# led_fading_circuit.net
KiCad netlist of a schematic drawn in EAGLE
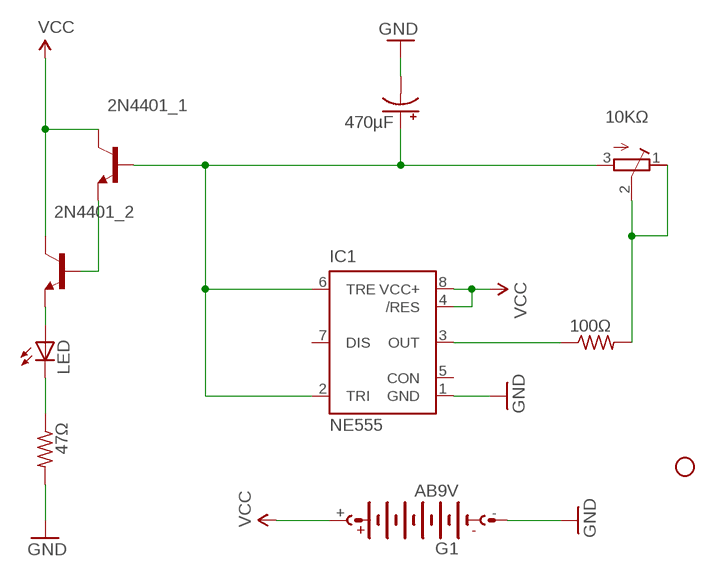
[diagram p0: schematic, sheet 1]

(export (version "E")
  (design (tool "Eeschema 10.0.6"))
  (components
    (comp (ref "2N4401_1")
      (value "-NPN-TO92-EBC")
      (footprint "eagle-import:TO92-EBC")
      (libsource (lib "eagle-import") (part "-NPN-TO92-EBC"))
    )
    (comp (ref "2N4401_2")
      (value "-NPN-TO92-EBC")
      (footprint "eagle-import:TO92-EBC")
      (libsource (lib "eagle-import") (part "-NPN-TO92-EBC"))
    )
    (comp (ref "10KΩ")
      (value "R-TRIMMT93XA")
      (footprint "eagle-import:RTRIMT93XA")
      (libsource (lib "eagle-import") (part "R-TRIMMT93XA"))
    )
    (comp (ref "47Ω")
      (value "R-US_0204/7")
      (footprint "eagle-import:0204_7")
      (libsource (lib "eagle-import") (part "R-US_0204/7"))
    )
    (comp (ref "100Ω")
      (value "R-US_0207/10")
      (footprint "eagle-import:0207_10")
      (libsource (lib "eagle-import") (part "R-US_0207/10"))
    )
    (comp (ref "470µF")
      (value "CPOL-USE2.5-6")
      (footprint "eagle-import:E2,5-6")
      (libsource (lib "eagle-import") (part "CPOL-USE2.5-6"))
    )
    (comp (ref "G1")
      (value "AB9V")
      (footprint "eagle-import:AB9V")
      (libsource (lib "eagle-import") (part "AB9V"))
    )
    (comp (ref "IC1")
      (value "NE555")
      (footprint "eagle-import:DIL-08")
      (fields (field (name "MF") "Arrow Electronics") (field (name "MPN") "NE555N"))
      (libsource (lib "eagle-import") (part "NE555"))
    )
    (comp (ref "LED")
      (value "LED5MM")
      (footprint "eagle-import:LED5MM")
      (libsource (lib "eagle-import") (part "LED5MM"))
    )
    (comp (ref "STANDOFF1")
      (value "STAND-OFF")
      (footprint "eagle-import:STAND-OFF")
      (libsource (lib "eagle-import") (part "STAND-OFF"))
    )
  )
  (nets
    (net (code "1") (name "GND") (class "Default")
      (node (ref "470µF") (pin "-") (pinfunction "-_-") (pintype "passive"))
      (node (ref "47Ω") (pin "2") (pinfunction "2_2") (pintype "passive"))
      (node (ref "G1") (pin "-") (pinfunction "-_-") (pintype "passive"))
      (node (ref "IC1") (pin "1") (pinfunction "GND_1") (pintype "power_in"))
    )
    (net (code "2") (name "Net-(2N4401_1-PadE)") (class "Default")
      (node (ref "2N4401_1") (pin "E") (pinfunction "E_E") (pintype "passive"))
      (node (ref "2N4401_2") (pin "B") (pinfunction "B_B") (pintype "passive"))
    )
    (net (code "3") (name "Net-(2N4401_2-PadE)") (class "Default")
      (node (ref "2N4401_2") (pin "E") (pinfunction "E_E") (pintype "passive"))
      (node (ref "LED") (pin "A") (pinfunction "A_A") (pintype "passive"))
    )
    (net (code "4") (name "Net-(10KΩ-A)") (class "Default")
      (node (ref "100Ω") (pin "2") (pinfunction "2_2") (pintype "passive"))
      (node (ref "10KΩ") (pin "1") (pinfunction "A_1") (pintype "passive"))
      (node (ref "10KΩ") (pin "2") (pinfunction "S_2") (pintype "passive"))
    )
    (net (code "5") (name "Net-(10KΩ-E)") (class "Default")
      (node (ref "10KΩ") (pin "3") (pinfunction "E_3") (pintype "passive"))
      (node (ref "2N4401_1") (pin "B") (pinfunction "B_B") (pintype "passive"))
      (node (ref "470µF") (pin "+") (pinfunction "+_+") (pintype "passive"))
      (node (ref "IC1") (pin "2") (pinfunction "TRI_2") (pintype "input"))
      (node (ref "IC1") (pin "6") (pinfunction "TRE_6") (pintype "input"))
    )
    (net (code "6") (name "Net-(IC1-OUT)") (class "Default")
      (node (ref "100Ω") (pin "1") (pinfunction "1_1") (pintype "passive"))
      (node (ref "IC1") (pin "3") (pinfunction "OUT_3") (pintype "output"))
    )
    (net (code "7") (name "Net-(LED-C)") (class "Default")
      (node (ref "47Ω") (pin "1") (pinfunction "1_1") (pintype "passive"))
      (node (ref "LED") (pin "K") (pinfunction "C_K") (pintype "passive"))
    )
    (net (code "8") (name "VCC") (class "Default")
      (node (ref "2N4401_1") (pin "C") (pinfunction "C_C") (pintype "passive"))
      (node (ref "2N4401_2") (pin "C") (pinfunction "C_C") (pintype "passive"))
      (node (ref "G1") (pin "+") (pinfunction "+_+") (pintype "passive"))
      (node (ref "IC1") (pin "4") (pinfunction "/RES_4") (pintype "input"))
      (node (ref "IC1") (pin "8") (pinfunction "VCC+_8") (pintype "power_in"))
    )
    (net (code "9") (name "unconnected-(IC1-CON-Pad5)") (class "Default")
      (node (ref "IC1") (pin "5") (pinfunction "CON_5") (pintype "input"))
    )
    (net (code "10") (name "unconnected-(IC1-DIS-Pad7)") (class "Default")
      (node (ref "IC1") (pin "7") (pinfunction "DIS_7") (pintype "input"))
    )
  )
)
